# POWER.net
KiCad netlist of a schematic drawn in Altium Designer
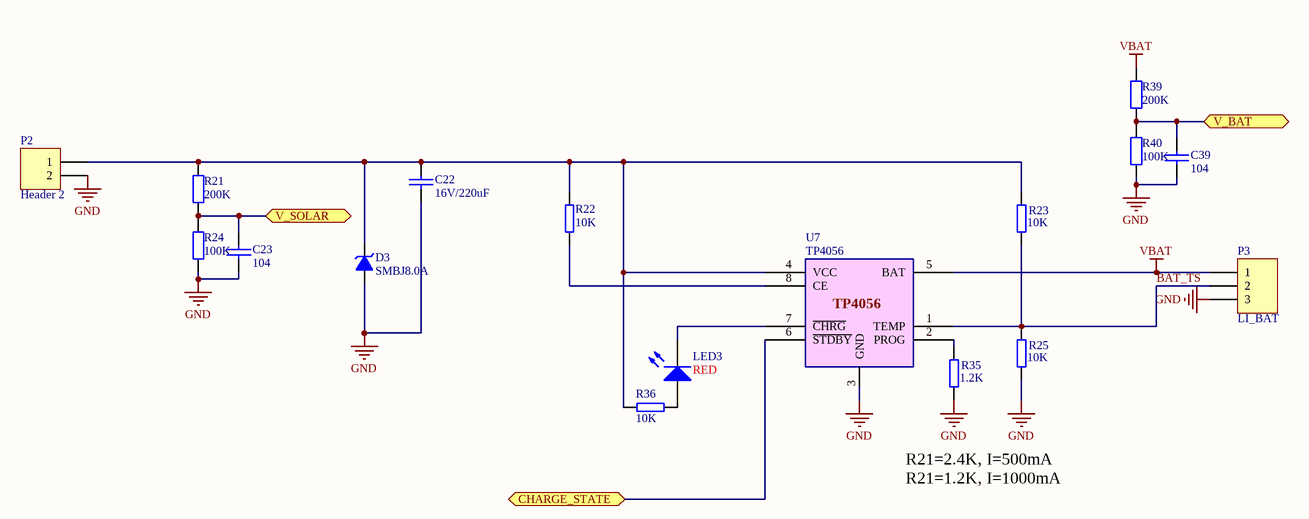
[diagram p0: POWER.SchDoc]

(export (version "E")
  (design (tool "Eeschema 10.0.6"))
  (components
    (comp (ref "C22") (value "16V/220uF") (footprint "CAP1210") (libsource (lib "Schlib") (part "0603C")))
    (comp (ref "C23") (value "104") (footprint "0603C") (libsource (lib "WT4815_CPU_Board") (part "0603C")))
    (comp (ref "C39") (value "104") (footprint "0603C") (libsource (lib "WT4815_CPU_Board") (part "0603C")))
    (comp (ref "D3")
      (value "SMBJ8.0A")
      (footprint "DO-214AA")
      (description "Zener Diode")
      (fields (field (name "PUBLISHER") "Altium Limited"))
      (libsource (lib "Calf") (part "D Zener"))
    )
    (comp (ref "LED3")
      (value "RED")
      (footprint "LED-0603")
      (description "RED LED")
      (fields (field (name "PUBLISHER") "Altium Limited"))
      (libsource (lib "Schlib") (part "LED3"))
    )
    (comp (ref "P2")
      (value "Header 2")
      (footprint "HEADER_2WAY_2.54MM")
      (description "Header, 2-Pin")
      (fields (field (name "PUBLISHER") "Altium Limited"))
      (libsource (lib "Miscellaneous Connectors") (part "Header 2"))
    )
    (comp (ref "P3")
      (value "LI_BAT")
      (footprint "HDR1X3_1.25mm")
      (description "Header, 3-Pin")
      (fields (field (name "PUBLISHER") "Altium Limited"))
      (libsource (lib "Miscellaneous Connectors") (part "Header 3"))
    )
    (comp (ref "R21") (value "200K") (footprint "0603R") (libsource (lib "WT4815_CPU_Board") (part "0603R")))
    (comp (ref "R22") (value "10K") (footprint "0603R") (libsource (lib "dtu02") (part "RES2A")))
    (comp (ref "R23") (value "10K") (footprint "0603R") (libsource (lib "dtu02") (part "RES2A")))
    (comp (ref "R24") (value "100K") (footprint "0603R") (libsource (lib "WT4815_CPU_Board") (part "0603R")))
    (comp (ref "R25") (value "10K") (footprint "0603R") (libsource (lib "dtu02") (part "RES2A")))
    (comp (ref "R35") (value "1.2K") (footprint "0603R") (libsource (lib "dtu02") (part "RES2A")))
    (comp (ref "R36") (value "10K") (footprint "0603R") (libsource (lib "dtu02") (part "RES2A")))
    (comp (ref "R39") (value "200K") (footprint "0603R") (libsource (lib "WT4815_CPU_Board") (part "0603R")))
    (comp (ref "R40") (value "100K") (footprint "0603R") (libsource (lib "WT4815_CPU_Board") (part "0603R")))
    (comp (ref "U7") (value "TP4056") (footprint "TP4056") (libsource (lib "SCT1212V100") (part "TP4056")))
  )
  (nets
    (net (code "1") (name "/BAT_TS") (class "Default")
      (node (ref "P3") (pin "2") (pinfunction "2_2") (pintype "passive"))
      (node (ref "R23") (pin "2") (pintype "passive"))
      (node (ref "R25") (pin "1") (pintype "passive"))
      (node (ref "U7") (pin "1") (pinfunction "TEMP_1") (pintype "passive"))
    )
    (net (code "2") (name "/CHARGE_STATE") (class "Default")
      (node (ref "U7") (pin "6") (pinfunction "~{STDBY}_6") (pintype "passive"))
    )
    (net (code "3") (name "/V_BAT") (class "Default")
      (node (ref "C39") (pin "2") (pintype "passive"))
      (node (ref "R39") (pin "2") (pinfunction "2_2") (pintype "passive"))
      (node (ref "R40") (pin "1") (pinfunction "1_1") (pintype "passive"))
    )
    (net (code "4") (name "/V_SOLAR") (class "Default")
      (node (ref "C23") (pin "2") (pintype "passive"))
      (node (ref "R21") (pin "2") (pinfunction "2_2") (pintype "passive"))
      (node (ref "R24") (pin "1") (pinfunction "1_1") (pintype "passive"))
    )
    (net (code "5") (name "GND") (class "Default")
      (node (ref "C22") (pin "2") (pintype "passive"))
      (node (ref "C23") (pin "1") (pintype "passive"))
      (node (ref "C39") (pin "1") (pintype "passive"))
      (node (ref "D3") (pin "1") (pinfunction "A_1") (pintype "passive"))
      (node (ref "P2") (pin "2") (pinfunction "2_2") (pintype "passive"))
      (node (ref "P3") (pin "3") (pinfunction "3_3") (pintype "passive"))
      (node (ref "R24") (pin "2") (pinfunction "2_2") (pintype "passive"))
      (node (ref "R25") (pin "2") (pintype "passive"))
      (node (ref "R35") (pin "2") (pintype "passive"))
      (node (ref "R40") (pin "2") (pinfunction "2_2") (pintype "passive"))
      (node (ref "U7") (pin "3") (pinfunction "GND_3") (pintype "passive"))
    )
    (net (code "6") (name "Net-(D3-K)") (class "Default")
      (node (ref "C22") (pin "1") (pintype "passive"))
      (node (ref "D3") (pin "2") (pinfunction "K_2") (pintype "passive"))
      (node (ref "P2") (pin "1") (pinfunction "1_1") (pintype "passive"))
      (node (ref "R21") (pin "1") (pinfunction "1_1") (pintype "passive"))
      (node (ref "R22") (pin "2") (pintype "passive"))
      (node (ref "R23") (pin "1") (pintype "passive"))
      (node (ref "R36") (pin "1") (pintype "passive"))
      (node (ref "U7") (pin "4") (pinfunction "VCC_4") (pintype "passive"))
    )
    (net (code "7") (name "Net-(LED3-A)") (class "Default")
      (node (ref "LED3") (pin "1") (pinfunction "A_1") (pintype "passive"))
      (node (ref "R36") (pin "2") (pintype "passive"))
    )
    (net (code "8") (name "Net-(LED3-K)") (class "Default")
      (node (ref "LED3") (pin "2") (pinfunction "K_2") (pintype "passive"))
      (node (ref "U7") (pin "7") (pinfunction "~{CHRG}_7") (pintype "passive"))
    )
    (net (code "9") (name "Net-(U7-CE)") (class "Default")
      (node (ref "R22") (pin "1") (pintype "passive"))
      (node (ref "U7") (pin "8") (pinfunction "CE_8") (pintype "passive"))
    )
    (net (code "10") (name "Net-(U7-PROG)") (class "Default")
      (node (ref "R35") (pin "1") (pintype "passive"))
      (node (ref "U7") (pin "2") (pinfunction "PROG_2") (pintype "passive"))
    )
    (net (code "11") (name "VBAT") (class "Default")
      (node (ref "P3") (pin "1") (pinfunction "1_1") (pintype "passive"))
      (node (ref "R39") (pin "1") (pinfunction "1_1") (pintype "passive"))
      (node (ref "U7") (pin "5") (pinfunction "BAT_5") (pintype "passive"))
    )
  )
)
